# ai_breakout_ds1307.net
KiCad netlist of a schematic drawn in EAGLE
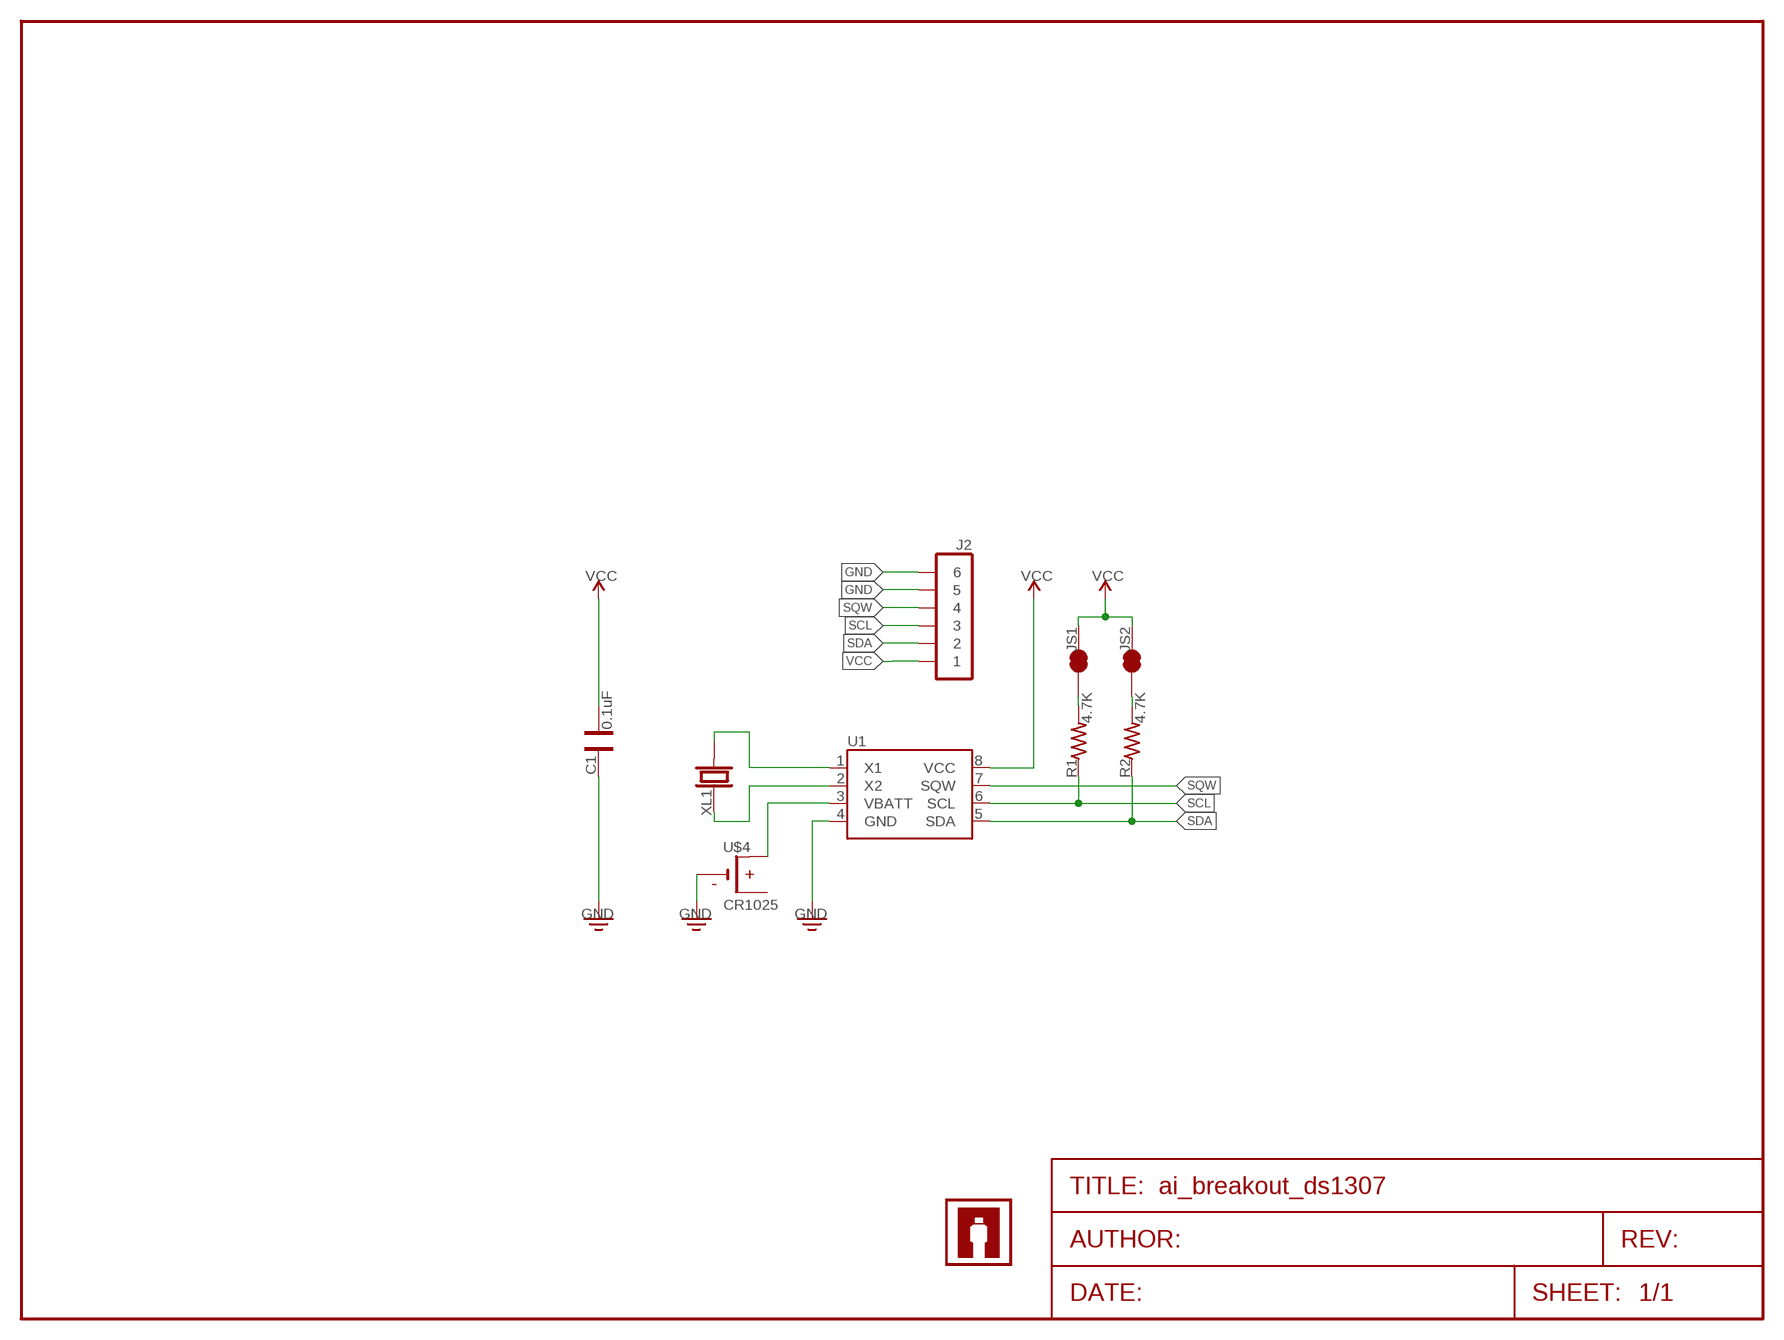
[diagram p0: schematic, sheet 1]

(export (version "E")
  (design (tool "Eeschema 10.0.6"))
  (components
    (comp (ref "C1")
      (value "0.1uF")
      (footprint "eagle-import:CAP-0603")
      (libsource (lib "eagle-import") (part "CAP0603"))
    )
    (comp (ref "J2")
      (value "1X06")
      (footprint "eagle-import:1X06")
      (libsource (lib "eagle-import") (part "1X06"))
    )
    (comp (ref "JS1")
      (value "1X02-SJ-NCT")
      (footprint "eagle-import:1X02-SJ-NCT")
      (libsource (lib "eagle-import") (part "1X02-SJ-NCT"))
    )
    (comp (ref "JS2")
      (value "1X02-SJ-NCT")
      (footprint "eagle-import:1X02-SJ-NCT")
      (libsource (lib "eagle-import") (part "1X02-SJ-NCT"))
    )
    (comp (ref "R1")
      (value "4.7K")
      (footprint "eagle-import:RES-0603")
      (libsource (lib "eagle-import") (part "RES0603"))
    )
    (comp (ref "R2")
      (value "4.7K")
      (footprint "eagle-import:RES-0603")
      (libsource (lib "eagle-import") (part "RES0603"))
    )
    (comp (ref "U$3")
      (value "AI-LOGOXS")
      (footprint "eagle-import:AI-LOGO-XS")
      (libsource (lib "eagle-import") (part "AI-LOGOXS"))
    )
    (comp (ref "U$4")
      (value "CR1025")
      (footprint "eagle-import:CR1025-SMD")
      (libsource (lib "eagle-import") (part "CR1025"))
    )
    (comp (ref "U1")
      (value "DS1307SO8")
      (footprint "eagle-import:SO08")
      (libsource (lib "eagle-import") (part "DS1307SO8"))
    )
    (comp (ref "XL1")
      (value "CRYSTALCYL-2X6MM-SMT")
      (footprint "eagle-import:CRYSTAL-CYL-2X6MM-SMT")
      (libsource (lib "eagle-import") (part "CRYSTALCYL-2X6MM-SMT"))
    )
  )
  (nets
    (net (code "1") (name "GND") (class "Default")
      (node (ref "C1") (pin "2") (pinfunction "2_2") (pintype "passive"))
      (node (ref "J2") (pin "5") (pinfunction "5_5") (pintype "bidirectional"))
      (node (ref "J2") (pin "6") (pinfunction "6_6") (pintype "bidirectional"))
      (node (ref "U$4") (pin "-") (pinfunction "-_-") (pintype "passive"))
      (node (ref "U1") (pin "4") (pinfunction "GND_4") (pintype "bidirectional"))
    )
    (net (code "2") (name "Net-(JS1-Pad1)") (class "Default")
      (node (ref "JS1") (pin "1") (pinfunction "1_1") (pintype "passive"))
      (node (ref "R1") (pin "2") (pinfunction "2_2") (pintype "passive"))
    )
    (net (code "3") (name "Net-(JS2-Pad1)") (class "Default")
      (node (ref "JS2") (pin "1") (pinfunction "1_1") (pintype "passive"))
      (node (ref "R2") (pin "2") (pinfunction "2_2") (pintype "passive"))
    )
    (net (code "4") (name "Net-(U1-VBATT)") (class "Default")
      (node (ref "U$4") (pin "+@1") (pinfunction "+1_+@1") (pintype "passive"))
      (node (ref "U$4") (pin "+@2") (pinfunction "+1_+@2") (pintype "passive"))
      (node (ref "U1") (pin "3") (pinfunction "VBATT_3") (pintype "bidirectional"))
    )
    (net (code "5") (name "Net-(U1-X1)") (class "Default")
      (node (ref "U1") (pin "1") (pinfunction "X1_1") (pintype "bidirectional"))
      (node (ref "XL1") (pin "2") (pinfunction "2_2") (pintype "passive"))
    )
    (net (code "6") (name "Net-(U1-X2)") (class "Default")
      (node (ref "U1") (pin "2") (pinfunction "X2_2") (pintype "bidirectional"))
      (node (ref "XL1") (pin "1") (pinfunction "1_1") (pintype "passive"))
    )
    (net (code "7") (name "SCL") (class "Default")
      (node (ref "J2") (pin "3") (pinfunction "3_3") (pintype "bidirectional"))
      (node (ref "R1") (pin "1") (pinfunction "1_1") (pintype "passive"))
      (node (ref "U1") (pin "6") (pinfunction "SCL_6") (pintype "bidirectional"))
    )
    (net (code "8") (name "SDA") (class "Default")
      (node (ref "J2") (pin "2") (pinfunction "2_2") (pintype "bidirectional"))
      (node (ref "R2") (pin "1") (pinfunction "1_1") (pintype "passive"))
      (node (ref "U1") (pin "5") (pinfunction "SDA_5") (pintype "bidirectional"))
    )
    (net (code "9") (name "SQW") (class "Default")
      (node (ref "J2") (pin "4") (pinfunction "4_4") (pintype "bidirectional"))
      (node (ref "U1") (pin "7") (pinfunction "SQW_7") (pintype "bidirectional"))
    )
    (net (code "10") (name "VCC") (class "Default")
      (node (ref "C1") (pin "1") (pinfunction "1_1") (pintype "passive"))
      (node (ref "J2") (pin "1") (pinfunction "1_1") (pintype "bidirectional"))
      (node (ref "JS1") (pin "2") (pinfunction "2_2") (pintype "passive"))
      (node (ref "JS2") (pin "2") (pinfunction "2_2") (pintype "passive"))
      (node (ref "U1") (pin "8") (pinfunction "VCC_8") (pintype "bidirectional"))
    )
  )
)
